# Device.net
KiCad netlist of a schematic drawn in Altium Designer
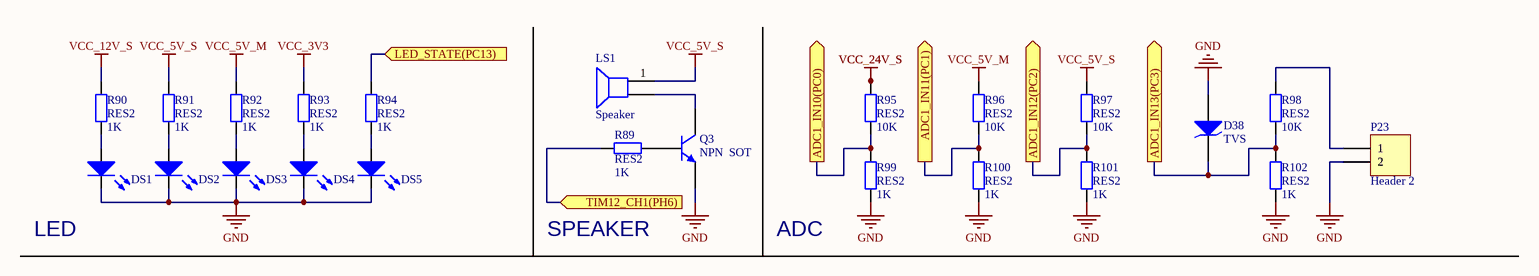
[diagram p0: Device.SchDoc]

(export (version "E")
  (design (tool "Eeschema 10.0.6"))
  (components
    (comp (ref "D38")
      (value "TVS")
      (footprint "SOD-523")
      (description "High Conductance Fast Diode")
      (fields (field (name "PUBLISHER") "Altium Limited"))
      (libsource (lib "QT") (part "D"))
    )
    (comp (ref "DS1") (value "LED") (footprint "LED 0805B") (libsource (lib "QT") (part "LED")))
    (comp (ref "DS2") (value "LED") (footprint "LED 0805B") (libsource (lib "QT") (part "LED")))
    (comp (ref "DS3") (value "LED") (footprint "LED 0805B") (libsource (lib "QT") (part "LED")))
    (comp (ref "DS4") (value "LED") (footprint "LED 0805B") (libsource (lib "QT") (part "LED")))
    (comp (ref "DS5") (value "LED") (footprint "LED 0805B") (libsource (lib "QT") (part "LED")))
    (comp (ref "LS1")
      (value "Speaker")
      (footprint "BEEP 5x9x5.5")
      (description "Loudspeaker")
      (fields (field (name "PUBLISHER") "Altium Limited"))
      (libsource (lib "QT") (part "Speaker"))
    )
    (comp (ref "P23")
      (value "Header 2")
      (footprint "HDR2.54-LI-2P")
      (description "Header, 2-Pin")
      (fields (field (name "PUBLISHER") "Altium Limited"))
      (libsource (lib "QT") (part "Header 2"))
    )
    (comp (ref "Q3")
      (value "NPN  SOT")
      (footprint "SOT23-3L")
      (description "NPN Bipolar Transistor")
      (fields (field (name "PUBLISHER") "Altium Limited"))
      (libsource (lib "QT") (part "NPN  SOT"))
    )
    (comp (ref "R89")
      (value "RES2")
      (footprint "R 0805_L")
      (description "Resistor")
      (fields (field (name "ALTIUM_VALUE") "1K") (field (name "PUBLISHER") "Altium Limited"))
      (libsource (lib "") (part "RES2_1"))
    )
    (comp (ref "R90")
      (value "RES2")
      (footprint "R 0805_L")
      (description "Resistor")
      (fields (field (name "ALTIUM_VALUE") "1K") (field (name "PUBLISHER") "Altium Limited"))
      (libsource (lib "QT") (part "RES2"))
    )
    (comp (ref "R91")
      (value "RES2")
      (footprint "R 0805_L")
      (description "Resistor")
      (fields (field (name "ALTIUM_VALUE") "1K") (field (name "PUBLISHER") "Altium Limited"))
      (libsource (lib "QT") (part "RES2"))
    )
    (comp (ref "R92")
      (value "RES2")
      (footprint "R 0805_L")
      (description "Resistor")
      (fields (field (name "ALTIUM_VALUE") "1K") (field (name "PUBLISHER") "Altium Limited"))
      (libsource (lib "QT") (part "RES2"))
    )
    (comp (ref "R93")
      (value "RES2")
      (footprint "R 0805_L")
      (description "Resistor")
      (fields (field (name "ALTIUM_VALUE") "1K") (field (name "PUBLISHER") "Altium Limited"))
      (libsource (lib "QT") (part "RES2"))
    )
    (comp (ref "R94")
      (value "RES2")
      (footprint "R 0805_L")
      (description "Resistor")
      (fields (field (name "ALTIUM_VALUE") "1K") (field (name "PUBLISHER") "Altium Limited"))
      (libsource (lib "QT") (part "RES2"))
    )
    (comp (ref "R95")
      (value "RES2")
      (footprint "R 0805_L")
      (description "Resistor")
      (fields (field (name "ALTIUM_VALUE") "10K") (field (name "PUBLISHER") "Altium Limited"))
      (libsource (lib "QT") (part "RES2"))
    )
    (comp (ref "R96")
      (value "RES2")
      (footprint "R 0805_L")
      (description "Resistor")
      (fields (field (name "ALTIUM_VALUE") "10K") (field (name "PUBLISHER") "Altium Limited"))
      (libsource (lib "QT") (part "RES2"))
    )
    (comp (ref "R97")
      (value "RES2")
      (footprint "R 0805_L")
      (description "Resistor")
      (fields (field (name "ALTIUM_VALUE") "10K") (field (name "PUBLISHER") "Altium Limited"))
      (libsource (lib "QT") (part "RES2"))
    )
    (comp (ref "R98")
      (value "RES2")
      (footprint "R 0805_L")
      (description "Resistor")
      (fields (field (name "ALTIUM_VALUE") "10K") (field (name "PUBLISHER") "Altium Limited"))
      (libsource (lib "QT") (part "RES2"))
    )
    (comp (ref "R99")
      (value "RES2")
      (footprint "R 0805_L")
      (description "Resistor")
      (fields (field (name "ALTIUM_VALUE") "1K") (field (name "PUBLISHER") "Altium Limited"))
      (libsource (lib "QT") (part "RES2"))
    )
    (comp (ref "R100")
      (value "RES2")
      (footprint "R 0805_L")
      (description "Resistor")
      (fields (field (name "ALTIUM_VALUE") "1K") (field (name "PUBLISHER") "Altium Limited"))
      (libsource (lib "QT") (part "RES2"))
    )
    (comp (ref "R101")
      (value "RES2")
      (footprint "R 0805_L")
      (description "Resistor")
      (fields (field (name "ALTIUM_VALUE") "1K") (field (name "PUBLISHER") "Altium Limited"))
      (libsource (lib "QT") (part "RES2"))
    )
    (comp (ref "R102")
      (value "RES2")
      (footprint "R 0805_L")
      (description "Resistor")
      (fields (field (name "ALTIUM_VALUE") "1K") (field (name "PUBLISHER") "Altium Limited"))
      (libsource (lib "QT") (part "RES2"))
    )
  )
  (nets
    (net (code "1") (name "/ADC1_IN10(PC0)") (class "Default")
      (node (ref "R95") (pin "1") (pinfunction "1_1") (pintype "passive"))
      (node (ref "R99") (pin "2") (pinfunction "2_2") (pintype "passive"))
    )
    (net (code "2") (name "/ADC1_IN11(PC1)") (class "Default")
      (node (ref "R100") (pin "2") (pinfunction "2_2") (pintype "passive"))
      (node (ref "R96") (pin "1") (pinfunction "1_1") (pintype "passive"))
    )
    (net (code "3") (name "/ADC1_IN12(PC2)") (class "Default")
      (node (ref "R101") (pin "2") (pinfunction "2_2") (pintype "passive"))
      (node (ref "R97") (pin "1") (pinfunction "1_1") (pintype "passive"))
    )
    (net (code "4") (name "/ADC1_IN13(PC3)") (class "Default")
      (node (ref "D38") (pin "2") (pinfunction "K_2") (pintype "passive"))
      (node (ref "R102") (pin "2") (pinfunction "2_2") (pintype "passive"))
      (node (ref "R98") (pin "1") (pinfunction "1_1") (pintype "passive"))
    )
    (net (code "5") (name "/LED_STATE(PC13)") (class "Default")
      (node (ref "R94") (pin "2") (pinfunction "2_2") (pintype "passive"))
    )
    (net (code "6") (name "/TIM12_CH1(PH6)") (class "Default")
      (node (ref "R89") (pin "2") (pinfunction "2_2") (pintype "passive"))
    )
    (net (code "7") (name "GND") (class "Default")
      (node (ref "D38") (pin "1") (pinfunction "A_1") (pintype "passive"))
      (node (ref "DS1") (pin "2") (pinfunction "K_2") (pintype "passive"))
      (node (ref "DS2") (pin "2") (pinfunction "K_2") (pintype "passive"))
      (node (ref "DS3") (pin "2") (pinfunction "K_2") (pintype "passive"))
      (node (ref "DS4") (pin "2") (pinfunction "K_2") (pintype "passive"))
      (node (ref "DS5") (pin "2") (pinfunction "K_2") (pintype "passive"))
      (node (ref "P23") (pin "2") (pinfunction "2_2") (pintype "passive"))
      (node (ref "Q3") (pin "2") (pinfunction "E_2") (pintype "passive"))
      (node (ref "R100") (pin "1") (pinfunction "1_1") (pintype "passive"))
      (node (ref "R101") (pin "1") (pinfunction "1_1") (pintype "passive"))
      (node (ref "R102") (pin "1") (pinfunction "1_1") (pintype "passive"))
      (node (ref "R99") (pin "1") (pinfunction "1_1") (pintype "passive"))
    )
    (net (code "8") (name "Net-(DS1-A)") (class "Default")
      (node (ref "DS1") (pin "1") (pinfunction "A_1") (pintype "passive"))
      (node (ref "R90") (pin "1") (pinfunction "1_1") (pintype "passive"))
    )
    (net (code "9") (name "Net-(DS2-A)") (class "Default")
      (node (ref "DS2") (pin "1") (pinfunction "A_1") (pintype "passive"))
      (node (ref "R91") (pin "1") (pinfunction "1_1") (pintype "passive"))
    )
    (net (code "10") (name "Net-(DS3-A)") (class "Default")
      (node (ref "DS3") (pin "1") (pinfunction "A_1") (pintype "passive"))
      (node (ref "R92") (pin "1") (pinfunction "1_1") (pintype "passive"))
    )
    (net (code "11") (name "Net-(DS4-A)") (class "Default")
      (node (ref "DS4") (pin "1") (pinfunction "A_1") (pintype "passive"))
      (node (ref "R93") (pin "1") (pinfunction "1_1") (pintype "passive"))
    )
    (net (code "12") (name "Net-(DS5-A)") (class "Default")
      (node (ref "DS5") (pin "1") (pinfunction "A_1") (pintype "passive"))
      (node (ref "R94") (pin "1") (pinfunction "1_1") (pintype "passive"))
    )
    (net (code "13") (name "Net-(P23-Pad1)") (class "Default")
      (node (ref "P23") (pin "1") (pinfunction "1_1") (pintype "passive"))
      (node (ref "R98") (pin "2") (pinfunction "2_2") (pintype "passive"))
    )
    (net (code "14") (name "Net-(Q3-B)") (class "Default")
      (node (ref "Q3") (pin "1") (pinfunction "B_1") (pintype "passive"))
      (node (ref "R89") (pin "1") (pinfunction "1_1") (pintype "passive"))
    )
    (net (code "15") (name "Net-(Q3-C)") (class "Default")
      (node (ref "LS1") (pin "2") (pinfunction "2_2") (pintype "passive"))
      (node (ref "Q3") (pin "3") (pinfunction "C_3") (pintype "passive"))
    )
    (net (code "16") (name "VCC_3V3") (class "Default")
      (node (ref "R93") (pin "2") (pinfunction "2_2") (pintype "passive"))
    )
    (net (code "17") (name "VCC_5V_M") (class "Default")
      (node (ref "R92") (pin "2") (pinfunction "2_2") (pintype "passive"))
      (node (ref "R96") (pin "2") (pinfunction "2_2") (pintype "passive"))
    )
    (net (code "18") (name "VCC_5V_S") (class "Default")
      (node (ref "LS1") (pin "1") (pinfunction "1_1") (pintype "passive"))
      (node (ref "R91") (pin "2") (pinfunction "2_2") (pintype "passive"))
      (node (ref "R97") (pin "2") (pinfunction "2_2") (pintype "passive"))
    )
    (net (code "19") (name "VCC_12V_S") (class "Default")
      (node (ref "R90") (pin "2") (pinfunction "2_2") (pintype "passive"))
    )
    (net (code "20") (name "VCC_24V_S") (class "Default")
      (node (ref "R95") (pin "2") (pinfunction "2_2") (pintype "passive"))
    )
  )
)
